# Microcontroller.net
KiCad netlist of a schematic drawn in Altium Designer
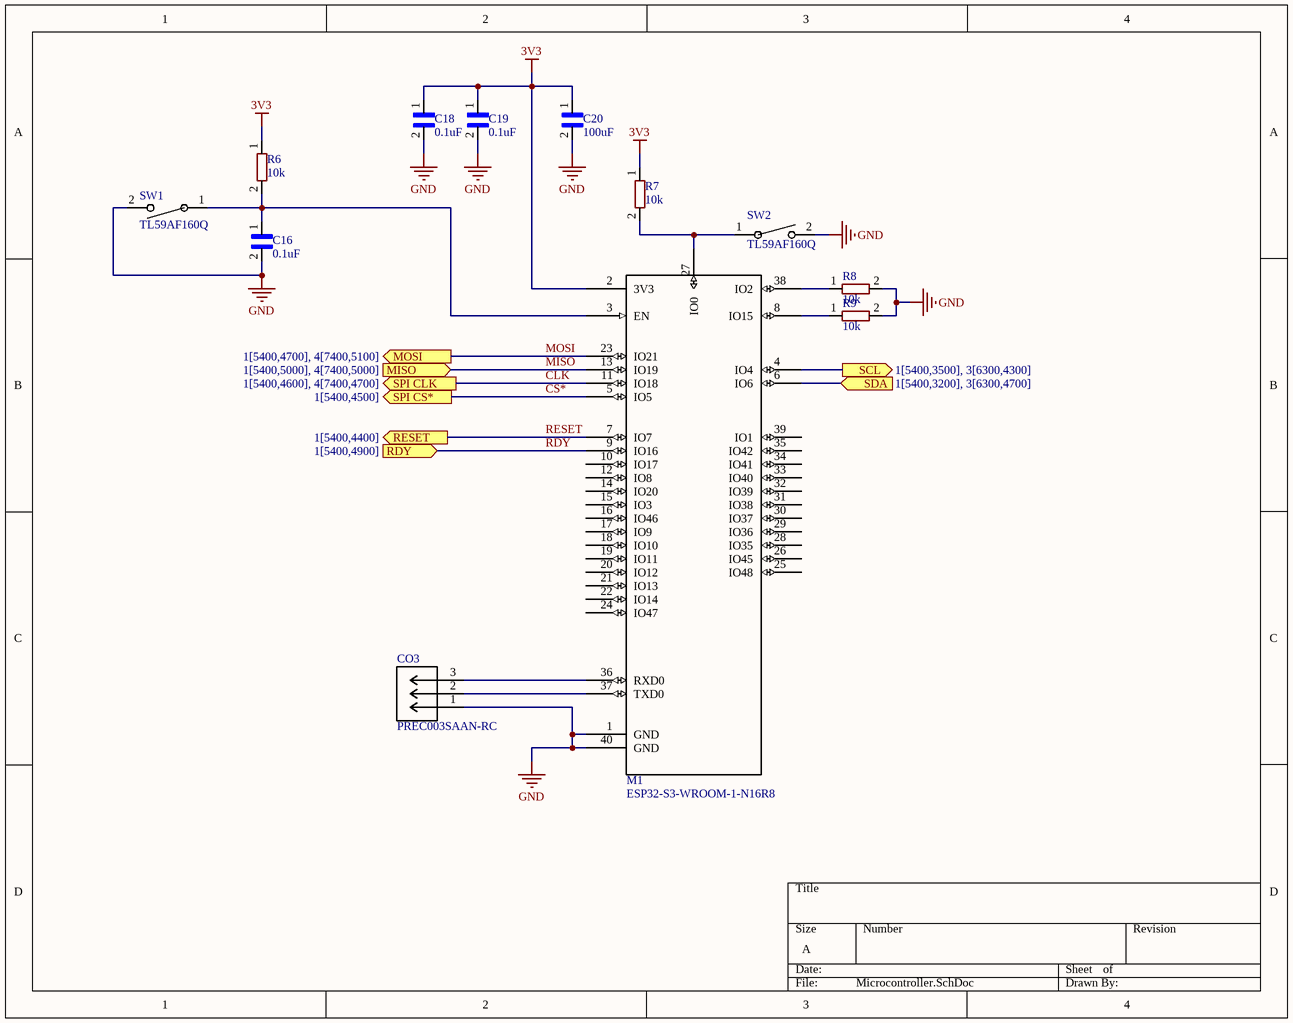
[diagram p0: Microcontroller.SchDoc]

(export (version "E")
  (design (tool "Eeschema 10.0.6"))
  (components
    (comp (ref "C16")
      (value "0.1uF")
      (footprint "0.1uF Capacitor")
      (description "No Description Available")
      (libsource (lib "0.1uF Capacitor") (part "CC1206JRX7R9BB104"))
    )
    (comp (ref "C18")
      (value "0.1uF")
      (footprint "0.1uF Capacitor")
      (description "No Description Available")
      (libsource (lib "0.1uF Capacitor") (part "CC1206JRX7R9BB104"))
    )
    (comp (ref "C19")
      (value "0.1uF")
      (footprint "0.1uF Capacitor")
      (description "No Description Available")
      (libsource (lib "0.1uF Capacitor") (part "CC1206JRX7R9BB104"))
    )
    (comp (ref "C20")
      (value "100uF")
      (footprint "CAPC3216X190N")
      (fields (field (name "MP") "GRM31CR60J107MEA8K"))
      (libsource (lib "100uf Capacitor") (part "GRM31CR60J107MEA8K"))
    )
    (comp (ref "CO3")
      (value "PREC003SAAN-RC")
      (footprint "CONN_PREC003SAAN-RC_SUL")
      (description "No Description Available")
      (libsource (lib "USB Connector") (part "PREC003SAAN-RC"))
    )
    (comp (ref "M1")
      (value "ESP32-S3-WROOM-1-N16R8")
      (footprint "ESP32-S3-WROOM-1_EXP")
      (description "No Description Available")
      (libsource (lib "ESP32-S3-WROOM-1-N16R8") (part "ESP32-S3-WROOM-1-N16R8"))
    )
    (comp (ref "R6")
      (value "10k")
      (footprint "10K Resistor:0603")
      (description "http://octopart.com/rc0603fr-1310kl-yageo+%2F+phycomp-25905087")
      (fields (field (name "MP") "RC0603FR-1310KL"))
      (libsource (lib "10K Resistor") (part "RC0603FR-1310KL"))
    )
    (comp (ref "R7")
      (value "10k")
      (footprint "10K Resistor:0603")
      (description "http://octopart.com/rc0603fr-1310kl-yageo+%2F+phycomp-25905087")
      (fields (field (name "MP") "RC0603FR-1310KL"))
      (libsource (lib "10K Resistor") (part "RC0603FR-1310KL"))
    )
    (comp (ref "R8")
      (value "10k")
      (footprint "10K Resistor:0603")
      (description "http://octopart.com/rc0603fr-1310kl-yageo+%2F+phycomp-25905087")
      (fields (field (name "MP") "RC0603FR-1310KL"))
      (libsource (lib "") (part "RC0603FR-1310KL_1"))
    )
    (comp (ref "R9")
      (value "10k")
      (footprint "10K Resistor:0603")
      (description "http://octopart.com/rc0603fr-1310kl-yageo+%2F+phycomp-25905087")
      (fields (field (name "MP") "RC0603FR-1310KL"))
      (libsource (lib "") (part "RC0603FR-1310KL_1"))
    )
    (comp (ref "SW1")
      (value "TL59AF160Q")
      (footprint "SW_TL59AF160Q_EWI")
      (description "No Description Available")
      (libsource (lib "Push Button") (part "TL59AF160Q"))
    )
    (comp (ref "SW2")
      (value "TL59AF160Q")
      (footprint "SW_TL59AF160Q_EWI")
      (description "No Description Available")
      (libsource (lib "") (part "TL59AF160Q_1"))
    )
  )
  (nets
    (net (code "1") (name "/CLK") (class "Default")
      (node (ref "M1") (pin "11") (pinfunction "IO18_11") (pintype "bidirectional"))
    )
    (net (code "2") (name "/CS*") (class "Default")
      (node (ref "M1") (pin "5") (pinfunction "IO5_5") (pintype "bidirectional"))
    )
    (net (code "3") (name "/MISO") (class "Default")
      (node (ref "M1") (pin "13") (pinfunction "IO19_13") (pintype "bidirectional"))
    )
    (net (code "4") (name "/MOSI") (class "Default")
      (node (ref "M1") (pin "23") (pinfunction "IO21_23") (pintype "bidirectional"))
    )
    (net (code "5") (name "/RDY") (class "Default")
      (node (ref "M1") (pin "9") (pinfunction "IO16_9") (pintype "bidirectional"))
    )
    (net (code "6") (name "/RESET") (class "Default")
      (node (ref "M1") (pin "7") (pinfunction "IO7_7") (pintype "bidirectional"))
    )
    (net (code "7") (name "/SCL") (class "Default")
      (node (ref "M1") (pin "4") (pinfunction "IO4_4") (pintype "bidirectional"))
    )
    (net (code "8") (name "/SDA") (class "Default")
      (node (ref "M1") (pin "6") (pinfunction "IO6_6") (pintype "bidirectional"))
    )
    (net (code "9") (name "3V3") (class "Default")
      (node (ref "C18") (pin "1") (pintype "passive"))
      (node (ref "C19") (pin "1") (pintype "passive"))
      (node (ref "C20") (pin "1") (pinfunction "1_1") (pintype "passive"))
      (node (ref "M1") (pin "2") (pinfunction "3V3_2") (pintype "power_in"))
      (node (ref "R6") (pin "1") (pintype "passive"))
      (node (ref "R7") (pin "1") (pintype "passive"))
    )
    (net (code "10") (name "GND") (class "Default")
      (node (ref "C16") (pin "2") (pintype "passive"))
      (node (ref "C18") (pin "2") (pintype "passive"))
      (node (ref "C19") (pin "2") (pintype "passive"))
      (node (ref "C20") (pin "2") (pinfunction "2_2") (pintype "passive"))
      (node (ref "CO3") (pin "1") (pinfunction "1_1") (pintype "passive"))
      (node (ref "M1") (pin "1") (pinfunction "GND_1") (pintype "power_in"))
      (node (ref "M1") (pin "40") (pinfunction "GND_40") (pintype "power_in"))
      (node (ref "R8") (pin "2") (pintype "passive"))
      (node (ref "R9") (pin "2") (pintype "passive"))
      (node (ref "SW1") (pin "2") (pinfunction "2_2") (pintype "passive"))
      (node (ref "SW2") (pin "2") (pinfunction "2_2") (pintype "passive"))
    )
    (net (code "11") (name "Net-(M1-EN)") (class "Default")
      (node (ref "C16") (pin "1") (pintype "passive"))
      (node (ref "M1") (pin "3") (pinfunction "EN_3") (pintype "input"))
      (node (ref "R6") (pin "2") (pintype "passive"))
      (node (ref "SW1") (pin "1") (pinfunction "1_1") (pintype "passive"))
    )
    (net (code "12") (name "Net-(M1-IO0)") (class "Default")
      (node (ref "M1") (pin "27") (pinfunction "IO0_27") (pintype "bidirectional"))
      (node (ref "R7") (pin "2") (pintype "passive"))
      (node (ref "SW2") (pin "1") (pinfunction "1_1") (pintype "passive"))
    )
    (net (code "13") (name "Net-(M1-IO2)") (class "Default")
      (node (ref "M1") (pin "38") (pinfunction "IO2_38") (pintype "bidirectional"))
      (node (ref "R8") (pin "1") (pintype "passive"))
    )
    (net (code "14") (name "Net-(M1-IO15)") (class "Default")
      (node (ref "M1") (pin "8") (pinfunction "IO15_8") (pintype "bidirectional"))
      (node (ref "R9") (pin "1") (pintype "passive"))
    )
    (net (code "15") (name "Net-(M1-RXD0)") (class "Default")
      (node (ref "CO3") (pin "3") (pinfunction "3_3") (pintype "passive"))
      (node (ref "M1") (pin "36") (pinfunction "RXD0_36") (pintype "bidirectional"))
    )
    (net (code "16") (name "Net-(M1-TXD0)") (class "Default")
      (node (ref "CO3") (pin "2") (pinfunction "2_2") (pintype "passive"))
      (node (ref "M1") (pin "37") (pinfunction "TXD0_37") (pintype "bidirectional"))
    )
    (net (code "17") (name "unconnected-(M1-IO1-Pad39)") (class "Default")
      (node (ref "M1") (pin "39") (pinfunction "IO1_39") (pintype "bidirectional"))
    )
    (net (code "18") (name "unconnected-(M1-IO3-Pad15)") (class "Default")
      (node (ref "M1") (pin "15") (pinfunction "IO3_15") (pintype "bidirectional"))
    )
    (net (code "19") (name "unconnected-(M1-IO8-Pad12)") (class "Default")
      (node (ref "M1") (pin "12") (pinfunction "IO8_12") (pintype "bidirectional"))
    )
    (net (code "20") (name "unconnected-(M1-IO9-Pad17)") (class "Default")
      (node (ref "M1") (pin "17") (pinfunction "IO9_17") (pintype "bidirectional"))
    )
    (net (code "21") (name "unconnected-(M1-IO10-Pad18)") (class "Default")
      (node (ref "M1") (pin "18") (pinfunction "IO10_18") (pintype "bidirectional"))
    )
    (net (code "22") (name "unconnected-(M1-IO11-Pad19)") (class "Default")
      (node (ref "M1") (pin "19") (pinfunction "IO11_19") (pintype "bidirectional"))
    )
    (net (code "23") (name "unconnected-(M1-IO12-Pad20)") (class "Default")
      (node (ref "M1") (pin "20") (pinfunction "IO12_20") (pintype "bidirectional"))
    )
    (net (code "24") (name "unconnected-(M1-IO13-Pad21)") (class "Default")
      (node (ref "M1") (pin "21") (pinfunction "IO13_21") (pintype "bidirectional"))
    )
    (net (code "25") (name "unconnected-(M1-IO14-Pad22)") (class "Default")
      (node (ref "M1") (pin "22") (pinfunction "IO14_22") (pintype "bidirectional"))
    )
    (net (code "26") (name "unconnected-(M1-IO17-Pad10)") (class "Default")
      (node (ref "M1") (pin "10") (pinfunction "IO17_10") (pintype "bidirectional"))
    )
    (net (code "27") (name "unconnected-(M1-IO20-Pad14)") (class "Default")
      (node (ref "M1") (pin "14") (pinfunction "IO20_14") (pintype "bidirectional"))
    )
    (net (code "28") (name "unconnected-(M1-IO35-Pad28)") (class "Default")
      (node (ref "M1") (pin "28") (pinfunction "IO35_28") (pintype "bidirectional"))
    )
    (net (code "29") (name "unconnected-(M1-IO36-Pad29)") (class "Default")
      (node (ref "M1") (pin "29") (pinfunction "IO36_29") (pintype "bidirectional"))
    )
    (net (code "30") (name "unconnected-(M1-IO37-Pad30)") (class "Default")
      (node (ref "M1") (pin "30") (pinfunction "IO37_30") (pintype "bidirectional"))
    )
    (net (code "31") (name "unconnected-(M1-IO38-Pad31)") (class "Default")
      (node (ref "M1") (pin "31") (pinfunction "IO38_31") (pintype "bidirectional"))
    )
    (net (code "32") (name "unconnected-(M1-IO39-Pad32)") (class "Default")
      (node (ref "M1") (pin "32") (pinfunction "IO39_32") (pintype "bidirectional"))
    )
    (net (code "33") (name "unconnected-(M1-IO40-Pad33)") (class "Default")
      (node (ref "M1") (pin "33") (pinfunction "IO40_33") (pintype "bidirectional"))
    )
    (net (code "34") (name "unconnected-(M1-IO41-Pad34)") (class "Default")
      (node (ref "M1") (pin "34") (pinfunction "IO41_34") (pintype "bidirectional"))
    )
    (net (code "35") (name "unconnected-(M1-IO42-Pad35)") (class "Default")
      (node (ref "M1") (pin "35") (pinfunction "IO42_35") (pintype "bidirectional"))
    )
    (net (code "36") (name "unconnected-(M1-IO45-Pad26)") (class "Default")
      (node (ref "M1") (pin "26") (pinfunction "IO45_26") (pintype "bidirectional"))
    )
    (net (code "37") (name "unconnected-(M1-IO46-Pad16)") (class "Default")
      (node (ref "M1") (pin "16") (pinfunction "IO46_16") (pintype "bidirectional"))
    )
    (net (code "38") (name "unconnected-(M1-IO47-Pad24)") (class "Default")
      (node (ref "M1") (pin "24") (pinfunction "IO47_24") (pintype "bidirectional"))
    )
    (net (code "39") (name "unconnected-(M1-IO48-Pad25)") (class "Default")
      (node (ref "M1") (pin "25") (pinfunction "IO48_25") (pintype "bidirectional"))
    )
  )
)
